# USB.net
KiCad netlist of a schematic drawn in Altium Designer
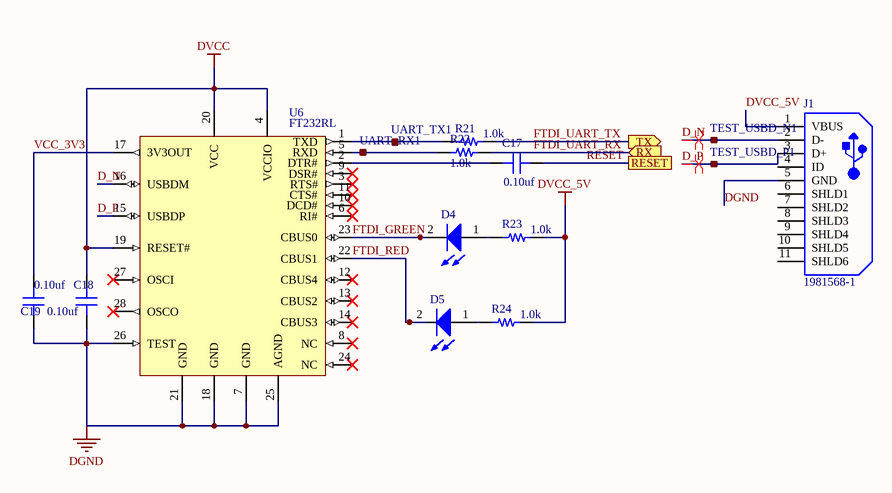
[diagram p0: USB.SchDoc]

(export (version "E")
  (design (tool "Eeschema 10.0.6"))
  (components
    (comp (ref "C17")
      (value "0.10uf")
      (footprint "CAP 0603/1608")
      (fields
        (field (name "Comment") "Capacitor MLCC 0.10uf 25V CAP 0603/1608")
        (field (name "CREATED_BY") "Nick Mah")
      )
      (libsource (lib "Altium-Lib") (part "Capacitor"))
    )
    (comp (ref "C18")
      (value "0.10uf")
      (footprint "CAP 0603/1608")
      (fields
        (field (name "Comment") "Capacitor MLCC 0.10uf 25V CAP 0603/1608")
        (field (name "CREATED_BY") "Nick Mah")
      )
      (libsource (lib "Altium-Lib") (part "Capacitor"))
    )
    (comp (ref "C19")
      (value "0.10uf")
      (footprint "CAP 0603/1608")
      (fields
        (field (name "Comment") "Capacitor MLCC 0.10uf 25V CAP 0603/1608")
        (field (name "CREATED_BY") "Nick Mah")
      )
      (libsource (lib "Altium-Lib") (part "Capacitor"))
    )
    (comp (ref "D4") (value "~") (footprint "0805_LED") (libsource (lib "Altium-Lib") (part "LED")))
    (comp (ref "D5") (value "~") (footprint "0805_LED") (libsource (lib "Altium-Lib") (part "LED")))
    (comp (ref "J1")
      (value "1981568-1")
      (footprint "TECO-1981568-5_V")
      (description "USB Micro Type B")
      (fields (field (name "CREATED_BY") "Aiku"))
      (libsource (lib "Altium-Lib") (part "USB-5-6SHLD"))
    )
    (comp (ref "R21")
      (value "1.0k")
      (footprint "RES 0805/2012")
      (fields
        (field (name "TOLERANCE") "1%")
        (field (name "POWER") "1/4W")
        (field (name "Comment") "Resistor 1.0k 0805 1/4W 1%")
        (field (name "CREATED_BY") "Nick Mah")
      )
      (libsource (lib "Altium-Lib") (part "Resistor"))
    )
    (comp (ref "R22")
      (value "1.0k")
      (footprint "RES 0805/2012")
      (fields
        (field (name "TOLERANCE") "1%")
        (field (name "POWER") "1/4W")
        (field (name "Comment") "Resistor 1.0k 0805 1/4W 1%")
        (field (name "CREATED_BY") "Nick Mah")
      )
      (libsource (lib "Altium-Lib") (part "Resistor"))
    )
    (comp (ref "R23")
      (value "1.0k")
      (footprint "RES 0805/2012")
      (fields
        (field (name "TOLERANCE") "1%")
        (field (name "POWER") "1/4W")
        (field (name "Comment") "Resistor 1.0k 0805 1/4W 1%")
        (field (name "CREATED_BY") "Nick Mah")
      )
      (libsource (lib "Altium-Lib") (part "Resistor"))
    )
    (comp (ref "R24")
      (value "1.0k")
      (footprint "RES 0805/2012")
      (fields
        (field (name "TOLERANCE") "1%")
        (field (name "POWER") "1/4W")
        (field (name "Comment") "Resistor 1.0k 0805 1/4W 1%")
        (field (name "CREATED_BY") "Nick Mah")
      )
      (libsource (lib "Altium-Lib") (part "Resistor"))
    )
    (comp (ref "TEST_USBD_N1")
      (value "RCU-0C")
      (footprint "RCU-0C")
      (libsource (lib "Altium-Lib") (part "RCU-0C"))
    )
    (comp (ref "TEST_USBD_P1")
      (value "RCU-0C")
      (footprint "RCU-0C")
      (libsource (lib "Altium-Lib") (part "RCU-0C"))
    )
    (comp (ref "U6")
      (value "FT232RL")
      (footprint "SSOP-28")
      (fields (field (name "CREATED_BY") "Kyle"))
      (libsource (lib "Altium-Lib") (part "FT232RL"))
    )
    (comp (ref "UART_RX1")
      (value "RCU-0C")
      (footprint "RCU-0C")
      (libsource (lib "Altium-Lib") (part "RCU-0C"))
    )
    (comp (ref "UART_TX1")
      (value "RCU-0C")
      (footprint "RCU-0C")
      (libsource (lib "Altium-Lib") (part "RCU-0C"))
    )
  )
  (nets
    (net (code "1") (name "/D_N") (class "Default")
      (node (ref "J1") (pin "2") (pinfunction "D-_2") (pintype "passive"))
      (node (ref "TEST_USBD_N1") (pin "1") (pintype "passive"))
      (node (ref "U6") (pin "16") (pinfunction "USBDM_16") (pintype "bidirectional"))
    )
    (net (code "2") (name "/D_P") (class "Default")
      (node (ref "J1") (pin "3") (pinfunction "D+_3") (pintype "passive"))
      (node (ref "TEST_USBD_P1") (pin "1") (pintype "passive"))
      (node (ref "U6") (pin "15") (pinfunction "USBDP_15") (pintype "bidirectional"))
    )
    (net (code "3") (name "/FTDI_GREEN") (class "Default")
      (node (ref "D4") (pin "2") (pinfunction "K_2") (pintype "passive"))
      (node (ref "U6") (pin "23") (pinfunction "CBUS0_23") (pintype "bidirectional"))
    )
    (net (code "4") (name "/FTDI_RED") (class "Default")
      (node (ref "D5") (pin "2") (pinfunction "K_2") (pintype "passive"))
      (node (ref "U6") (pin "22") (pinfunction "CBUS1_22") (pintype "bidirectional"))
    )
    (net (code "5") (name "/FTDI_UART_RX") (class "Default")
      (node (ref "R22") (pin "2") (pinfunction "2_2") (pintype "passive"))
    )
    (net (code "6") (name "/FTDI_UART_TX") (class "Default")
      (node (ref "R21") (pin "2") (pinfunction "2_2") (pintype "passive"))
    )
    (net (code "7") (name "/RESET") (class "Default")
      (node (ref "C17") (pin "2") (pinfunction "2_2") (pintype "passive"))
    )
    (net (code "8") (name "/VCC_3V3") (class "Default")
      (node (ref "C19") (pin "2") (pinfunction "2_2") (pintype "passive"))
      (node (ref "U6") (pin "17") (pinfunction "3V3OUT_17") (pintype "output"))
    )
    (net (code "9") (name "DGND") (class "Default")
      (node (ref "C18") (pin "1") (pinfunction "1_1") (pintype "passive"))
      (node (ref "C19") (pin "1") (pinfunction "1_1") (pintype "passive"))
      (node (ref "J1") (pin "5") (pinfunction "GND_5") (pintype "passive"))
      (node (ref "U6") (pin "18") (pinfunction "GND_18") (pintype "passive"))
      (node (ref "U6") (pin "21") (pinfunction "GND_21") (pintype "passive"))
      (node (ref "U6") (pin "25") (pinfunction "AGND_25") (pintype "passive"))
      (node (ref "U6") (pin "26") (pinfunction "TEST_26") (pintype "input"))
      (node (ref "U6") (pin "7") (pinfunction "GND_7") (pintype "passive"))
    )
    (net (code "10") (name "DVCC") (class "Default")
      (node (ref "C18") (pin "2") (pinfunction "2_2") (pintype "passive"))
      (node (ref "U6") (pin "19") (pinfunction "RESET#_19") (pintype "input"))
      (node (ref "U6") (pin "20") (pinfunction "VCC_20") (pintype "passive"))
      (node (ref "U6") (pin "4") (pinfunction "VCCIO_4") (pintype "passive"))
    )
    (net (code "11") (name "DVCC_5V") (class "Default")
      (node (ref "J1") (pin "1") (pinfunction "VBUS_1") (pintype "passive"))
      (node (ref "R23") (pin "2") (pinfunction "2_2") (pintype "passive"))
      (node (ref "R24") (pin "2") (pinfunction "2_2") (pintype "passive"))
    )
    (net (code "12") (name "Net-(D4-A)") (class "Default")
      (node (ref "D4") (pin "1") (pinfunction "A_1") (pintype "passive"))
      (node (ref "R23") (pin "1") (pinfunction "1_1") (pintype "passive"))
    )
    (net (code "13") (name "Net-(D5-A)") (class "Default")
      (node (ref "D5") (pin "1") (pinfunction "A_1") (pintype "passive"))
      (node (ref "R24") (pin "1") (pinfunction "1_1") (pintype "passive"))
    )
    (net (code "14") (name "Net-(U6-DTR#)") (class "Default")
      (node (ref "C17") (pin "1") (pinfunction "1_1") (pintype "passive"))
      (node (ref "U6") (pin "2") (pinfunction "DTR#_2") (pintype "output"))
    )
    (net (code "15") (name "Net-(U6-RXD)") (class "Default")
      (node (ref "R22") (pin "1") (pinfunction "1_1") (pintype "passive"))
      (node (ref "U6") (pin "5") (pinfunction "RXD_5") (pintype "input"))
      (node (ref "UART_RX1") (pin "1") (pintype "passive"))
    )
    (net (code "16") (name "Net-(U6-TXD)") (class "Default")
      (node (ref "R21") (pin "1") (pinfunction "1_1") (pintype "passive"))
      (node (ref "U6") (pin "1") (pinfunction "TXD_1") (pintype "output"))
      (node (ref "UART_TX1") (pin "1") (pintype "passive"))
    )
    (net (code "17") (name "unconnected-(J1-ID-Pad4)") (class "Default")
      (node (ref "J1") (pin "4") (pinfunction "ID_4") (pintype "passive"))
    )
    (net (code "18") (name "unconnected-(J1-SHLD1-Pad6)") (class "Default")
      (node (ref "J1") (pin "6") (pinfunction "SHLD1_6") (pintype "passive"))
    )
    (net (code "19") (name "unconnected-(J1-SHLD2-Pad7)") (class "Default")
      (node (ref "J1") (pin "7") (pinfunction "SHLD2_7") (pintype "passive"))
    )
    (net (code "20") (name "unconnected-(J1-SHLD3-Pad8)") (class "Default")
      (node (ref "J1") (pin "8") (pinfunction "SHLD3_8") (pintype "passive"))
    )
    (net (code "21") (name "unconnected-(J1-SHLD4-Pad9)") (class "Default")
      (node (ref "J1") (pin "9") (pinfunction "SHLD4_9") (pintype "passive"))
    )
    (net (code "22") (name "unconnected-(J1-SHLD5-Pad10)") (class "Default")
      (node (ref "J1") (pin "10") (pinfunction "SHLD5_10") (pintype "passive"))
    )
    (net (code "23") (name "unconnected-(J1-SHLD6-Pad11)") (class "Default")
      (node (ref "J1") (pin "11") (pinfunction "SHLD6_11") (pintype "passive"))
    )
    (net (code "24") (name "unconnected-(U6-CBUS2-Pad13)") (class "Default")
      (node (ref "U6") (pin "13") (pinfunction "CBUS2_13") (pintype "bidirectional+no_connect"))
    )
    (net (code "25") (name "unconnected-(U6-CBUS3-Pad14)") (class "Default")
      (node (ref "U6") (pin "14") (pinfunction "CBUS3_14") (pintype "bidirectional+no_connect"))
    )
    (net (code "26") (name "unconnected-(U6-CBUS4-Pad12)") (class "Default")
      (node (ref "U6") (pin "12") (pinfunction "CBUS4_12") (pintype "bidirectional+no_connect"))
    )
    (net (code "27") (name "unconnected-(U6-CTS#-Pad11)") (class "Default")
      (node (ref "U6") (pin "11") (pinfunction "CTS#_11") (pintype "input+no_connect"))
    )
    (net (code "28") (name "unconnected-(U6-DCD#-Pad10)") (class "Default")
      (node (ref "U6") (pin "10") (pinfunction "DCD#_10") (pintype "input+no_connect"))
    )
    (net (code "29") (name "unconnected-(U6-DSR#-Pad9)") (class "Default")
      (node (ref "U6") (pin "9") (pinfunction "DSR#_9") (pintype "input+no_connect"))
    )
    (net (code "30") (name "unconnected-(U6-NC-Pad8)") (class "Default")
      (node (ref "U6") (pin "8") (pinfunction "NC_8") (pintype "input+no_connect"))
    )
    (net (code "31") (name "unconnected-(U6-NC-Pad24)") (class "Default")
      (node (ref "U6") (pin "24") (pinfunction "NC_24") (pintype "input+no_connect"))
    )
    (net (code "32") (name "unconnected-(U6-OSCI-Pad27)") (class "Default")
      (node (ref "U6") (pin "27") (pinfunction "OSCI_27") (pintype "input+no_connect"))
    )
    (net (code "33") (name "unconnected-(U6-OSCO-Pad28)") (class "Default")
      (node (ref "U6") (pin "28") (pinfunction "OSCO_28") (pintype "output+no_connect"))
    )
    (net (code "34") (name "unconnected-(U6-RI#-Pad6)") (class "Default")
      (node (ref "U6") (pin "6") (pinfunction "RI#_6") (pintype "input+no_connect"))
    )
    (net (code "35") (name "unconnected-(U6-RTS#-Pad3)") (class "Default")
      (node (ref "U6") (pin "3") (pinfunction "RTS#_3") (pintype "output+no_connect"))
    )
  )
)
